# SCH_MODULO_CARGA.net
KiCad netlist of a schematic drawn in Altium Designer
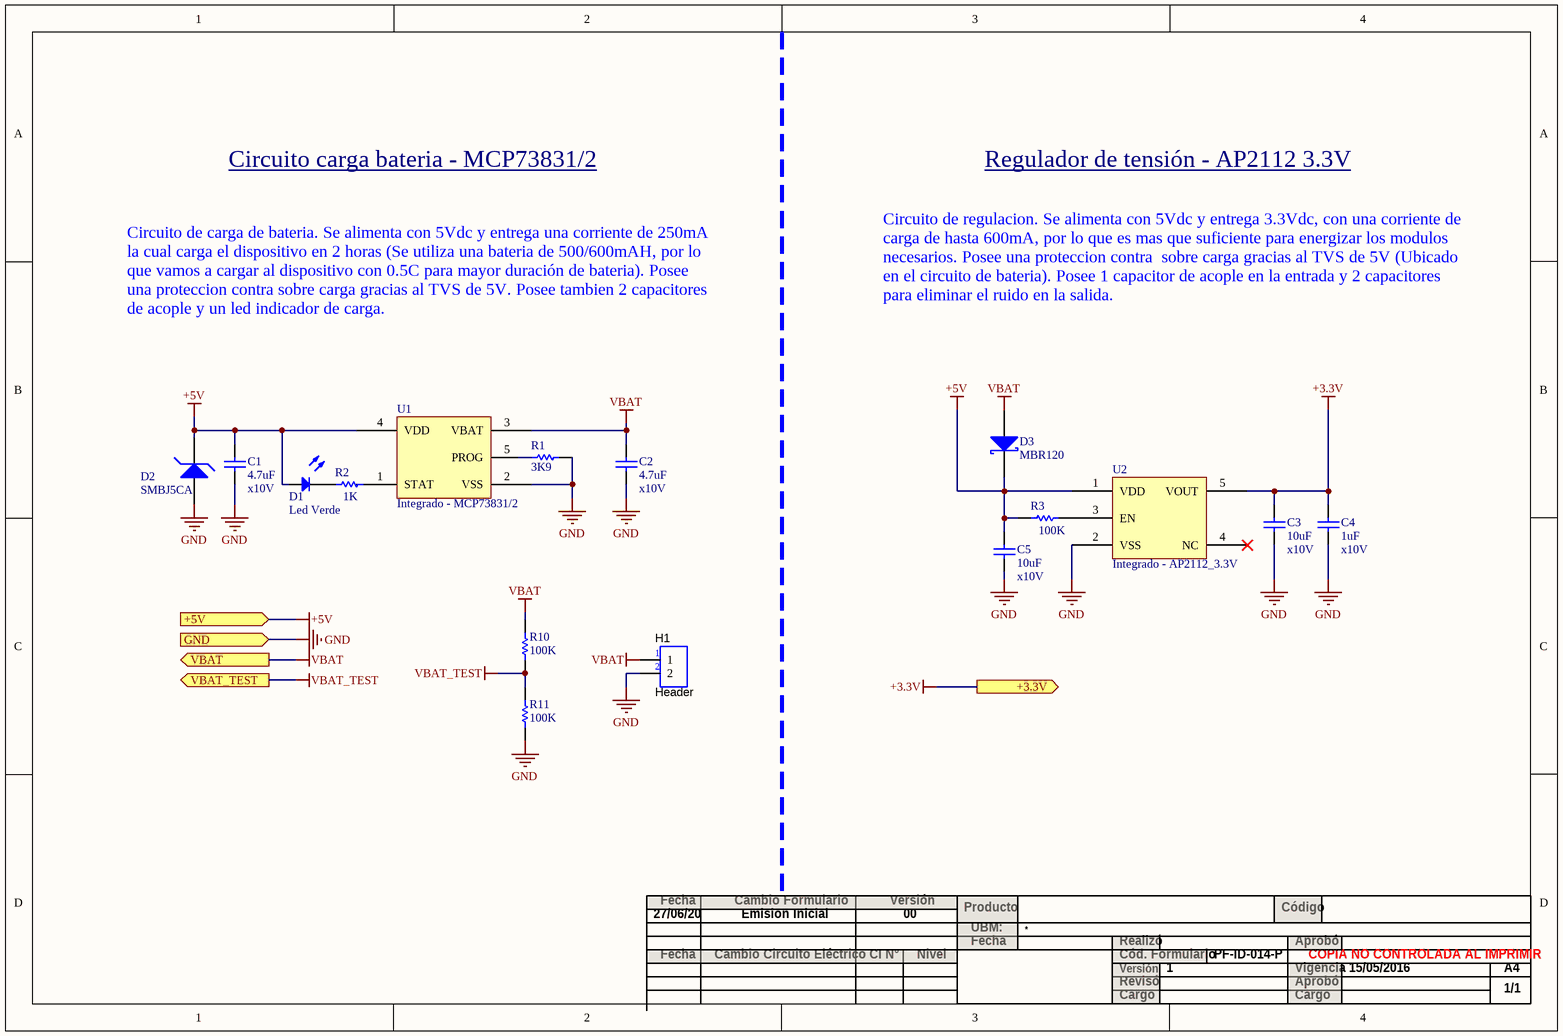
[diagram p0: SCH_MODULO_CARGA.SchDoc]

(export (version "E")
  (design (tool "Eeschema 10.0.6"))
  (components
    (comp (ref "C1")
      (value "4.7uF")
      (footprint "RAD-0.3")
      (description "Capacitor")
      (fields
        (field (name "VOLTAGE") "x10V")
        (field (name "Comment") "Capacitor - Común")
        (field (name "PUBLISHER") "Altium Limited")
      )
      (libsource (lib "LIB_COLLAR") (part "Capacitor - Común"))
    )
    (comp (ref "C2")
      (value "4.7uF")
      (footprint "RAD-0.3")
      (description "Capacitor")
      (fields
        (field (name "VOLTAGE") "x10V")
        (field (name "Comment") "Capacitor - Común")
        (field (name "PUBLISHER") "Altium Limited")
      )
      (libsource (lib "LIB_COLLAR") (part "Capacitor - Común"))
    )
    (comp (ref "C3")
      (value "10uF")
      (footprint "RAD-0.3")
      (description "Capacitor")
      (fields
        (field (name "VOLTAGE") "x10V")
        (field (name "Comment") "Capacitor - Común")
        (field (name "PUBLISHER") "Altium Limited")
      )
      (libsource (lib "LIB_COLLAR") (part "Capacitor - Común"))
    )
    (comp (ref "C4")
      (value "1uF")
      (footprint "RAD-0.3")
      (description "Capacitor")
      (fields
        (field (name "VOLTAGE") "x10V")
        (field (name "Comment") "Capacitor - Común")
        (field (name "PUBLISHER") "Altium Limited")
      )
      (libsource (lib "LIB_COLLAR") (part "Capacitor - Común"))
    )
    (comp (ref "C5")
      (value "10uF")
      (footprint "RAD-0.3")
      (description "Capacitor")
      (fields
        (field (name "VOLTAGE") "x10V")
        (field (name "Comment") "Capacitor - Común")
        (field (name "PUBLISHER") "Altium Limited")
      )
      (libsource (lib "LIB_COLLAR") (part "Capacitor - Común"))
    )
    (comp (ref "D1")
      (value "Led Verde")
      (footprint "LED-0")
      (description "Diodo Led")
      (fields (field (name "PUBLISHER") "Altium Limited"))
      (libsource (lib "LIB_COLLAR") (part "Diodo - LED"))
    )
    (comp (ref "D2")
      (value "SMBJ5CA")
      (footprint "SMC")
      (description "Default Diode")
      (fields (field (name "PUBLISHER") "Altium Limited"))
      (libsource (lib "LIB_COLLAR") (part "Diodo - TVS"))
    )
    (comp (ref "D3")
      (value "MBR120")
      (footprint "SMB")
      (description "Schottky Diode")
      (fields (field (name "PUBLISHER") "Altium Limited"))
      (libsource (lib "LIB_COLLAR") (part "Diodo - Schottky"))
    )
    (comp (ref "H1")
      (value "Header")
      (footprint "HDR_1x2_Offset")
      (description "Header, 2-pin")
      (libsource (lib "LIB_COLLAR") (part "Conector - 2 Pos"))
    )
    (comp (ref "R1")
      (value "3K9")
      (footprint "Res_0603")
      (description "Semiconductor Resistor")
      (fields (field (name "Comment") "Resistencia - Común") (field (name "PUBLISHER") "Altium Limited"))
      (libsource (lib "LIB_COLLAR") (part "Resistencia - Común"))
    )
    (comp (ref "R2")
      (value "1K")
      (footprint "Res_0603")
      (description "Semiconductor Resistor")
      (fields (field (name "Comment") "Resistencia - Común") (field (name "PUBLISHER") "Altium Limited"))
      (libsource (lib "LIB_COLLAR") (part "Resistencia - Común"))
    )
    (comp (ref "R3")
      (value "100K")
      (footprint "Res_0603")
      (description "Semiconductor Resistor")
      (fields (field (name "Comment") "Resistencia - Común") (field (name "PUBLISHER") "Altium Limited"))
      (libsource (lib "LIB_COLLAR") (part "Resistencia - Común"))
    )
    (comp (ref "R10")
      (value "100K")
      (footprint "AXIAL-0.5")
      (description "Semiconductor Resistor")
      (fields (field (name "Comment") "Resistencia - Común") (field (name "PUBLISHER") "Altium Limited"))
      (libsource (lib "LIB_COLLAR") (part "Resistencia - Común"))
    )
    (comp (ref "R11")
      (value "100K")
      (footprint "AXIAL-0.5")
      (description "Semiconductor Resistor")
      (fields (field (name "Comment") "Resistencia - Común") (field (name "PUBLISHER") "Altium Limited"))
      (libsource (lib "LIB_COLLAR") (part "Resistencia - Común"))
    )
    (comp (ref "U1")
      (value "Integrado - MCP73831/2")
      (footprint "SOT23-5")
      (description "Cargador bateria Litio 3,7V")
      (libsource (lib "LIB_COLLAR") (part "Integrado - MCP73831/2"))
    )
    (comp (ref "U2")
      (value "Integrado - AP2112_3.3V")
      (footprint "SOT23-5")
      (description "Regulador 3.3V 600mA")
      (libsource (lib "LIB_COLLAR") (part "Integrado - AP2112_3.3V"))
    )
  )
  (nets
    (net (code "1") (name "+3.3V") (class "Default")
      (node (ref "C3") (pin "2") (pinfunction "2_2") (pintype "passive"))
      (node (ref "C4") (pin "2") (pinfunction "2_2") (pintype "passive"))
      (node (ref "U2") (pin "5") (pinfunction "VOUT_5") (pintype "passive"))
    )
    (net (code "2") (name "+5V") (class "Default")
      (node (ref "C1") (pin "1") (pinfunction "1_1") (pintype "passive"))
      (node (ref "C5") (pin "2") (pinfunction "2_2") (pintype "passive"))
      (node (ref "D1") (pin "1") (pinfunction "A_1") (pintype "passive"))
      (node (ref "D2") (pin "2") (pinfunction "K_2") (pintype "passive"))
      (node (ref "D3") (pin "2") (pinfunction "K_2") (pintype "passive"))
      (node (ref "R3") (pin "1") (pinfunction "1_1") (pintype "passive"))
      (node (ref "U1") (pin "4") (pinfunction "VDD_4") (pintype "power_in"))
      (node (ref "U2") (pin "1") (pinfunction "VDD_1") (pintype "passive"))
    )
    (net (code "3") (name "GND") (class "Default")
      (node (ref "C1") (pin "2") (pinfunction "2_2") (pintype "passive"))
      (node (ref "C2") (pin "1") (pinfunction "1_1") (pintype "passive"))
      (node (ref "C3") (pin "1") (pinfunction "1_1") (pintype "passive"))
      (node (ref "C4") (pin "1") (pinfunction "1_1") (pintype "passive"))
      (node (ref "C5") (pin "1") (pinfunction "1_1") (pintype "passive"))
      (node (ref "D2") (pin "1") (pinfunction "A_1") (pintype "passive"))
      (node (ref "H1") (pin "2") (pinfunction "2_2") (pintype "passive"))
      (node (ref "R1") (pin "2") (pinfunction "2_2") (pintype "passive"))
      (node (ref "R11") (pin "1") (pinfunction "1_1") (pintype "passive"))
      (node (ref "U1") (pin "2") (pinfunction "VSS_2") (pintype "power_in"))
      (node (ref "U2") (pin "2") (pinfunction "VSS_2") (pintype "power_in"))
    )
    (net (code "4") (name "Net-(D1-K)") (class "Default")
      (node (ref "D1") (pin "2") (pinfunction "K_2") (pintype "passive"))
      (node (ref "R2") (pin "1") (pinfunction "1_1") (pintype "passive"))
    )
    (net (code "5") (name "Net-(U1-PROG)") (class "Default")
      (node (ref "R1") (pin "1") (pinfunction "1_1") (pintype "passive"))
      (node (ref "U1") (pin "5") (pinfunction "PROG_5") (pintype "passive"))
    )
    (net (code "6") (name "Net-(U2-EN)") (class "Default")
      (node (ref "R3") (pin "2") (pinfunction "2_2") (pintype "passive"))
      (node (ref "U2") (pin "3") (pinfunction "EN_3") (pintype "passive"))
    )
    (net (code "7") (name "VBAT") (class "Default")
      (node (ref "C2") (pin "2") (pinfunction "2_2") (pintype "passive"))
      (node (ref "D3") (pin "1") (pinfunction "A_1") (pintype "passive"))
      (node (ref "H1") (pin "1") (pinfunction "1_1") (pintype "passive"))
      (node (ref "R10") (pin "2") (pinfunction "2_2") (pintype "passive"))
      (node (ref "U1") (pin "3") (pinfunction "VBAT_3") (pintype "passive"))
    )
    (net (code "8") (name "VBAT_TEST") (class "Default")
      (node (ref "R10") (pin "1") (pinfunction "1_1") (pintype "passive"))
      (node (ref "R11") (pin "2") (pinfunction "2_2") (pintype "passive"))
    )
    (net (code "9") (name "unconnected-(R2-Pad2)") (class "Default")
      (node (ref "R2") (pin "2") (pinfunction "2_2") (pintype "passive"))
    )
    (net (code "10") (name "unconnected-(U1-STAT-Pad1)") (class "Default")
      (node (ref "U1") (pin "1") (pinfunction "STAT_1") (pintype "passive"))
    )
    (net (code "11") (name "unconnected-(U2-NC-Pad4)") (class "Default")
      (node (ref "U2") (pin "4") (pinfunction "NC_4") (pintype "power_in+no_connect"))
    )
  )
)
